# SCH_mpu6050_2024-04-15.net
KiCad netlist of a schematic drawn in EasyEDA
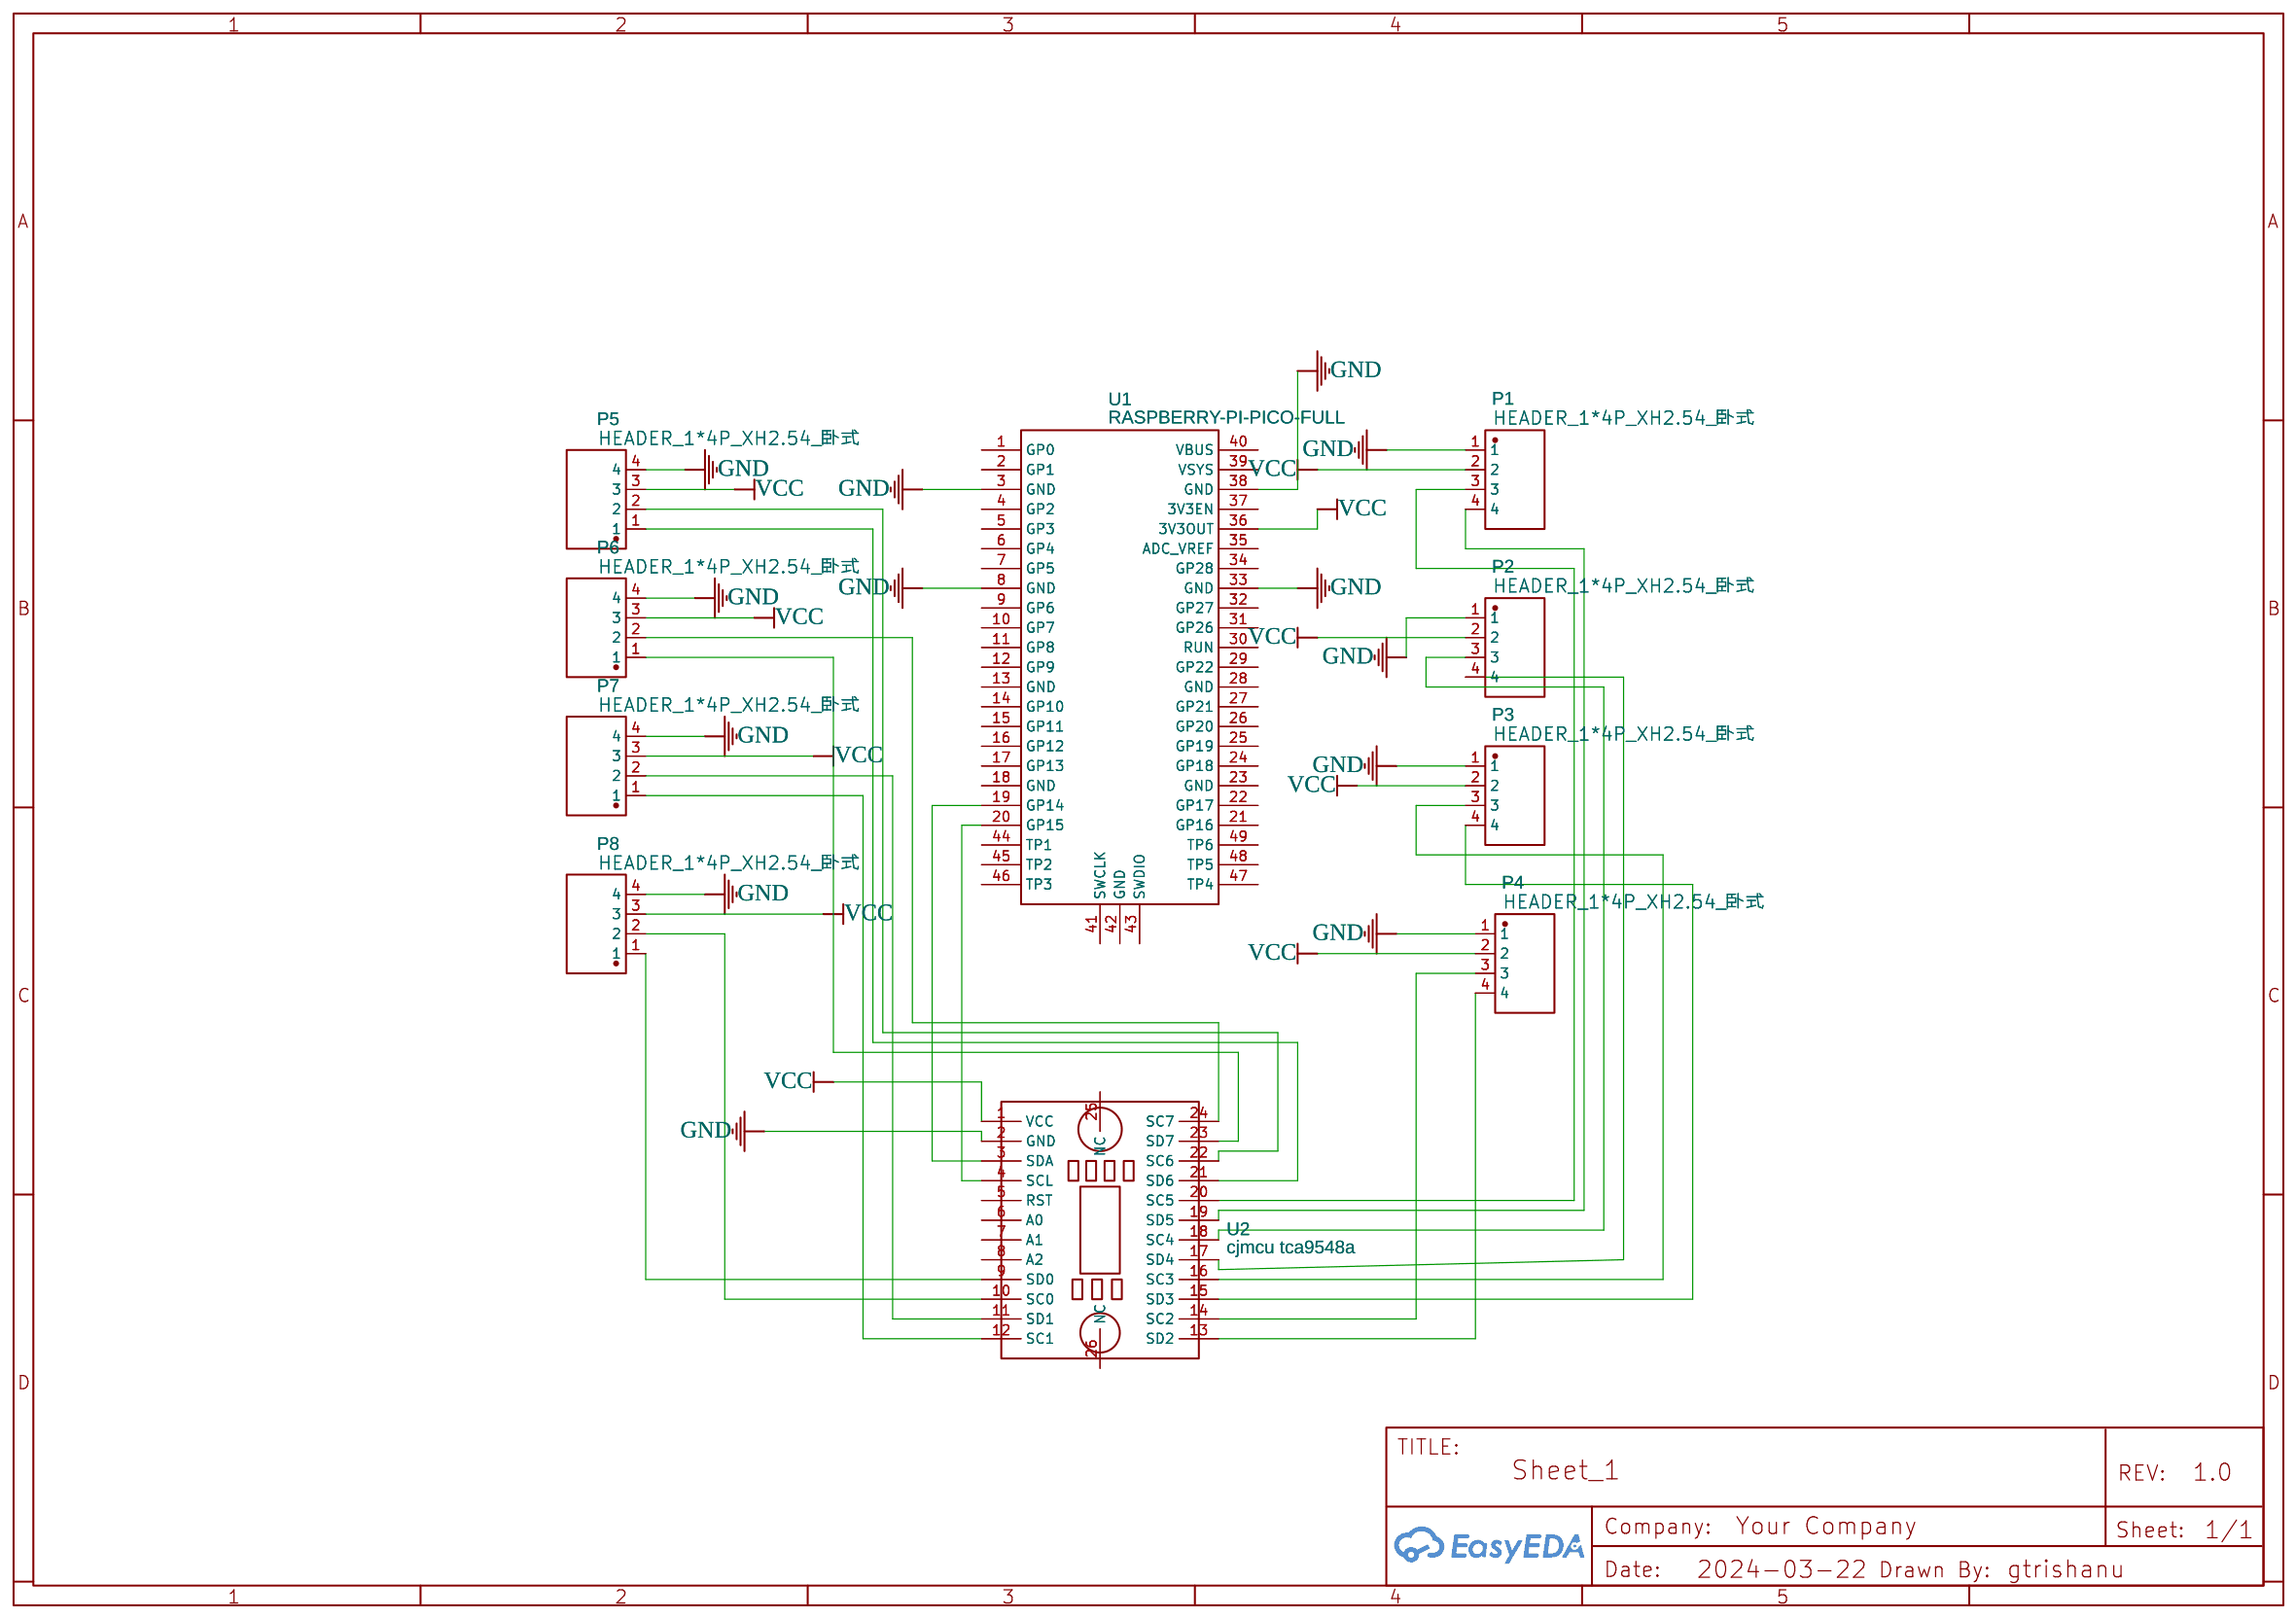
[diagram p0: schematic sheet]

(export (version "E")
  (design (tool "Eeschema 10.0.6"))
  (components
    (comp (ref "P1") (value "HEADER_1*4P_XH2.54_卧式") (libsource (lib "") (part "HEADER_1*4P_XH2.54_卧式")))
    (comp (ref "P2") (value "HEADER_1*4P_XH2.54_卧式") (libsource (lib "") (part "HEADER_1*4P_XH2.54_卧式")))
    (comp (ref "P3") (value "HEADER_1*4P_XH2.54_卧式") (libsource (lib "") (part "HEADER_1*4P_XH2.54_卧式")))
    (comp (ref "P4") (value "HEADER_1*4P_XH2.54_卧式") (libsource (lib "") (part "HEADER_1*4P_XH2.54_卧式")))
    (comp (ref "P5") (value "HEADER_1*4P_XH2.54_卧式") (libsource (lib "") (part "HEADER_1*4P_XH2.54_卧式_1")))
    (comp (ref "P6") (value "HEADER_1*4P_XH2.54_卧式") (libsource (lib "") (part "HEADER_1*4P_XH2.54_卧式_1")))
    (comp (ref "P7") (value "HEADER_1*4P_XH2.54_卧式") (libsource (lib "") (part "HEADER_1*4P_XH2.54_卧式_1")))
    (comp (ref "P8") (value "HEADER_1*4P_XH2.54_卧式") (libsource (lib "") (part "HEADER_1*4P_XH2.54_卧式_1")))
    (comp (ref "U1")
      (value "RASPBERRY-PI-PICO-FULL")
      (fields
        (field (name "Manufacturer Part") "Raspberry Pi Pico")
        (field (name "Manufacturer") "Raspberry Pi Foundation")
      )
      (libsource (lib "") (part "RASPBERRY-PI-PICO-FULL"))
    )
    (comp (ref "U2") (value "cjmcu tca9548a") (libsource (lib "") (part "cjmcu tca9548a")))
  )
  (nets
    (net (code "1") (name "GND") (class "Default")
      (node (ref "P1") (pin "1") (pinfunction "1_1") (pintype "unspecified"))
      (node (ref "P2") (pin "1") (pinfunction "1_1") (pintype "unspecified"))
      (node (ref "P3") (pin "1") (pinfunction "1_1") (pintype "unspecified"))
      (node (ref "P4") (pin "1") (pinfunction "1_1") (pintype "unspecified"))
      (node (ref "P5") (pin "4") (pinfunction "4_4") (pintype "unspecified"))
      (node (ref "P6") (pin "4") (pinfunction "4_4") (pintype "unspecified"))
      (node (ref "P7") (pin "4") (pinfunction "4_4") (pintype "unspecified"))
      (node (ref "P8") (pin "4") (pinfunction "4_4") (pintype "unspecified"))
      (node (ref "U1") (pin "3") (pinfunction "GND_3") (pintype "unspecified"))
      (node (ref "U1") (pin "33") (pinfunction "GND_33") (pintype "unspecified"))
      (node (ref "U1") (pin "38") (pinfunction "GND_38") (pintype "unspecified"))
      (node (ref "U1") (pin "8") (pinfunction "GND_8") (pintype "unspecified"))
      (node (ref "U2") (pin "2") (pinfunction "GND_2") (pintype "unspecified"))
    )
    (net (code "2") (name "Net-(U1-GP14)") (class "Default")
      (node (ref "U1") (pin "19") (pinfunction "GP14_19") (pintype "unspecified"))
      (node (ref "U2") (pin "3") (pinfunction "SDA_3") (pintype "unspecified"))
    )
    (net (code "3") (name "Net-(U1-GP15)") (class "Default")
      (node (ref "U1") (pin "20") (pinfunction "GP15_20") (pintype "unspecified"))
      (node (ref "U2") (pin "4") (pinfunction "SCL_4") (pintype "unspecified"))
    )
    (net (code "4") (name "Net-(U2-SC0)") (class "Default")
      (node (ref "P8") (pin "2") (pinfunction "2_2") (pintype "unspecified"))
      (node (ref "U2") (pin "10") (pinfunction "SC0_10") (pintype "unspecified"))
    )
    (net (code "5") (name "Net-(U2-SC1)") (class "Default")
      (node (ref "P7") (pin "1") (pinfunction "1_1") (pintype "unspecified"))
      (node (ref "U2") (pin "12") (pinfunction "SC1_12") (pintype "unspecified"))
    )
    (net (code "6") (name "Net-(U2-SC2)") (class "Default")
      (node (ref "P4") (pin "3") (pinfunction "3_3") (pintype "unspecified"))
      (node (ref "U2") (pin "14") (pinfunction "SC2_14") (pintype "unspecified"))
    )
    (net (code "7") (name "Net-(U2-SC3)") (class "Default")
      (node (ref "P3") (pin "3") (pinfunction "3_3") (pintype "unspecified"))
      (node (ref "U2") (pin "16") (pinfunction "SC3_16") (pintype "unspecified"))
    )
    (net (code "8") (name "Net-(U2-SC4)") (class "Default")
      (node (ref "P2") (pin "3") (pinfunction "3_3") (pintype "unspecified"))
      (node (ref "U2") (pin "18") (pinfunction "SC4_18") (pintype "unspecified"))
    )
    (net (code "9") (name "Net-(U2-SC5)") (class "Default")
      (node (ref "P1") (pin "3") (pinfunction "3_3") (pintype "unspecified"))
      (node (ref "U2") (pin "20") (pinfunction "SC5_20") (pintype "unspecified"))
    )
    (net (code "10") (name "Net-(U2-SC6)") (class "Default")
      (node (ref "P5") (pin "2") (pinfunction "2_2") (pintype "unspecified"))
      (node (ref "U2") (pin "22") (pinfunction "SC6_22") (pintype "unspecified"))
    )
    (net (code "11") (name "Net-(U2-SC7)") (class "Default")
      (node (ref "P6") (pin "2") (pinfunction "2_2") (pintype "unspecified"))
      (node (ref "U2") (pin "24") (pinfunction "SC7_24") (pintype "unspecified"))
    )
    (net (code "12") (name "Net-(U2-SD0)") (class "Default")
      (node (ref "P8") (pin "1") (pinfunction "1_1") (pintype "unspecified"))
      (node (ref "U2") (pin "9") (pinfunction "SD0_9") (pintype "unspecified"))
    )
    (net (code "13") (name "Net-(U2-SD1)") (class "Default")
      (node (ref "P7") (pin "2") (pinfunction "2_2") (pintype "unspecified"))
      (node (ref "U2") (pin "11") (pinfunction "SD1_11") (pintype "unspecified"))
    )
    (net (code "14") (name "Net-(U2-SD2)") (class "Default")
      (node (ref "P4") (pin "4") (pinfunction "4_4") (pintype "unspecified"))
      (node (ref "U2") (pin "13") (pinfunction "SD2_13") (pintype "unspecified"))
    )
    (net (code "15") (name "Net-(U2-SD3)") (class "Default")
      (node (ref "P3") (pin "4") (pinfunction "4_4") (pintype "unspecified"))
      (node (ref "U2") (pin "15") (pinfunction "SD3_15") (pintype "unspecified"))
    )
    (net (code "16") (name "Net-(U2-SD4)") (class "Default")
      (node (ref "P2") (pin "4") (pinfunction "4_4") (pintype "unspecified"))
      (node (ref "U2") (pin "17") (pinfunction "SD4_17") (pintype "unspecified"))
    )
    (net (code "17") (name "Net-(U2-SD5)") (class "Default")
      (node (ref "P1") (pin "4") (pinfunction "4_4") (pintype "unspecified"))
      (node (ref "U2") (pin "19") (pinfunction "SD5_19") (pintype "unspecified"))
    )
    (net (code "18") (name "Net-(U2-SD6)") (class "Default")
      (node (ref "P5") (pin "1") (pinfunction "1_1") (pintype "unspecified"))
      (node (ref "U2") (pin "21") (pinfunction "SD6_21") (pintype "unspecified"))
    )
    (net (code "19") (name "Net-(U2-SD7)") (class "Default")
      (node (ref "P6") (pin "1") (pinfunction "1_1") (pintype "unspecified"))
      (node (ref "U2") (pin "23") (pinfunction "SD7_23") (pintype "unspecified"))
    )
    (net (code "20") (name "VCC") (class "Default")
      (node (ref "P1") (pin "2") (pinfunction "2_2") (pintype "unspecified"))
      (node (ref "P2") (pin "2") (pinfunction "2_2") (pintype "unspecified"))
      (node (ref "P3") (pin "2") (pinfunction "2_2") (pintype "unspecified"))
      (node (ref "P4") (pin "2") (pinfunction "2_2") (pintype "unspecified"))
      (node (ref "P5") (pin "3") (pinfunction "3_3") (pintype "unspecified"))
      (node (ref "P6") (pin "3") (pinfunction "3_3") (pintype "unspecified"))
      (node (ref "P7") (pin "3") (pinfunction "3_3") (pintype "unspecified"))
      (node (ref "P8") (pin "3") (pinfunction "3_3") (pintype "unspecified"))
      (node (ref "U1") (pin "36") (pinfunction "3V3OUT_36") (pintype "unspecified"))
      (node (ref "U2") (pin "1") (pinfunction "VCC_1") (pintype "unspecified"))
    )
    (net (code "21") (name "unconnected-(U1-3V3EN-Pad37)") (class "Default")
      (node (ref "U1") (pin "37") (pinfunction "3V3EN_37") (pintype "unspecified"))
    )
    (net (code "22") (name "unconnected-(U1-ADC_VREF-Pad35)") (class "Default")
      (node (ref "U1") (pin "35") (pinfunction "ADC_VREF_35") (pintype "unspecified"))
    )
    (net (code "23") (name "unconnected-(U1-GND-Pad13)") (class "Default")
      (node (ref "U1") (pin "13") (pinfunction "GND_13") (pintype "unspecified"))
    )
    (net (code "24") (name "unconnected-(U1-GND-Pad18)") (class "Default")
      (node (ref "U1") (pin "18") (pinfunction "GND_18") (pintype "unspecified"))
    )
    (net (code "25") (name "unconnected-(U1-GND-Pad23)") (class "Default")
      (node (ref "U1") (pin "23") (pinfunction "GND_23") (pintype "unspecified"))
    )
    (net (code "26") (name "unconnected-(U1-GND-Pad28)") (class "Default")
      (node (ref "U1") (pin "28") (pinfunction "GND_28") (pintype "unspecified"))
    )
    (net (code "27") (name "unconnected-(U1-GND-Pad42)") (class "Default")
      (node (ref "U1") (pin "42") (pinfunction "GND_42") (pintype "unspecified"))
    )
    (net (code "28") (name "unconnected-(U1-GP0-Pad1)") (class "Default")
      (node (ref "U1") (pin "1") (pinfunction "GP0_1") (pintype "unspecified"))
    )
    (net (code "29") (name "unconnected-(U1-GP1-Pad2)") (class "Default")
      (node (ref "U1") (pin "2") (pinfunction "GP1_2") (pintype "unspecified"))
    )
    (net (code "30") (name "unconnected-(U1-GP2-Pad4)") (class "Default")
      (node (ref "U1") (pin "4") (pinfunction "GP2_4") (pintype "unspecified"))
    )
    (net (code "31") (name "unconnected-(U1-GP3-Pad5)") (class "Default")
      (node (ref "U1") (pin "5") (pinfunction "GP3_5") (pintype "unspecified"))
    )
    (net (code "32") (name "unconnected-(U1-GP4-Pad6)") (class "Default")
      (node (ref "U1") (pin "6") (pinfunction "GP4_6") (pintype "unspecified"))
    )
    (net (code "33") (name "unconnected-(U1-GP5-Pad7)") (class "Default")
      (node (ref "U1") (pin "7") (pinfunction "GP5_7") (pintype "unspecified"))
    )
    (net (code "34") (name "unconnected-(U1-GP6-Pad9)") (class "Default")
      (node (ref "U1") (pin "9") (pinfunction "GP6_9") (pintype "unspecified"))
    )
    (net (code "35") (name "unconnected-(U1-GP7-Pad10)") (class "Default")
      (node (ref "U1") (pin "10") (pinfunction "GP7_10") (pintype "unspecified"))
    )
    (net (code "36") (name "unconnected-(U1-GP8-Pad11)") (class "Default")
      (node (ref "U1") (pin "11") (pinfunction "GP8_11") (pintype "unspecified"))
    )
    (net (code "37") (name "unconnected-(U1-GP9-Pad12)") (class "Default")
      (node (ref "U1") (pin "12") (pinfunction "GP9_12") (pintype "unspecified"))
    )
    (net (code "38") (name "unconnected-(U1-GP10-Pad14)") (class "Default")
      (node (ref "U1") (pin "14") (pinfunction "GP10_14") (pintype "unspecified"))
    )
    (net (code "39") (name "unconnected-(U1-GP11-Pad15)") (class "Default")
      (node (ref "U1") (pin "15") (pinfunction "GP11_15") (pintype "unspecified"))
    )
    (net (code "40") (name "unconnected-(U1-GP12-Pad16)") (class "Default")
      (node (ref "U1") (pin "16") (pinfunction "GP12_16") (pintype "unspecified"))
    )
    (net (code "41") (name "unconnected-(U1-GP13-Pad17)") (class "Default")
      (node (ref "U1") (pin "17") (pinfunction "GP13_17") (pintype "unspecified"))
    )
    (net (code "42") (name "unconnected-(U1-GP16-Pad21)") (class "Default")
      (node (ref "U1") (pin "21") (pinfunction "GP16_21") (pintype "unspecified"))
    )
    (net (code "43") (name "unconnected-(U1-GP17-Pad22)") (class "Default")
      (node (ref "U1") (pin "22") (pinfunction "GP17_22") (pintype "unspecified"))
    )
    (net (code "44") (name "unconnected-(U1-GP18-Pad24)") (class "Default")
      (node (ref "U1") (pin "24") (pinfunction "GP18_24") (pintype "unspecified"))
    )
    (net (code "45") (name "unconnected-(U1-GP19-Pad25)") (class "Default")
      (node (ref "U1") (pin "25") (pinfunction "GP19_25") (pintype "unspecified"))
    )
    (net (code "46") (name "unconnected-(U1-GP20-Pad26)") (class "Default")
      (node (ref "U1") (pin "26") (pinfunction "GP20_26") (pintype "unspecified"))
    )
    (net (code "47") (name "unconnected-(U1-GP21-Pad27)") (class "Default")
      (node (ref "U1") (pin "27") (pinfunction "GP21_27") (pintype "unspecified"))
    )
    (net (code "48") (name "unconnected-(U1-GP22-Pad29)") (class "Default")
      (node (ref "U1") (pin "29") (pinfunction "GP22_29") (pintype "unspecified"))
    )
    (net (code "49") (name "unconnected-(U1-GP26-Pad31)") (class "Default")
      (node (ref "U1") (pin "31") (pinfunction "GP26_31") (pintype "unspecified"))
    )
    (net (code "50") (name "unconnected-(U1-GP27-Pad32)") (class "Default")
      (node (ref "U1") (pin "32") (pinfunction "GP27_32") (pintype "unspecified"))
    )
    (net (code "51") (name "unconnected-(U1-GP28-Pad34)") (class "Default")
      (node (ref "U1") (pin "34") (pinfunction "GP28_34") (pintype "unspecified"))
    )
    (net (code "52") (name "unconnected-(U1-RUN-Pad30)") (class "Default")
      (node (ref "U1") (pin "30") (pinfunction "RUN_30") (pintype "unspecified"))
    )
    (net (code "53") (name "unconnected-(U1-SWCLK-Pad41)") (class "Default")
      (node (ref "U1") (pin "41") (pinfunction "SWCLK_41") (pintype "unspecified"))
    )
    (net (code "54") (name "unconnected-(U1-SWDIO-Pad43)") (class "Default")
      (node (ref "U1") (pin "43") (pinfunction "SWDIO_43") (pintype "unspecified"))
    )
    (net (code "55") (name "unconnected-(U1-TP1-Pad44)") (class "Default")
      (node (ref "U1") (pin "44") (pinfunction "TP1_44") (pintype "unspecified"))
    )
    (net (code "56") (name "unconnected-(U1-TP2-Pad45)") (class "Default")
      (node (ref "U1") (pin "45") (pinfunction "TP2_45") (pintype "unspecified"))
    )
    (net (code "57") (name "unconnected-(U1-TP3-Pad46)") (class "Default")
      (node (ref "U1") (pin "46") (pinfunction "TP3_46") (pintype "unspecified"))
    )
    (net (code "58") (name "unconnected-(U1-TP4-Pad47)") (class "Default")
      (node (ref "U1") (pin "47") (pinfunction "TP4_47") (pintype "unspecified"))
    )
    (net (code "59") (name "unconnected-(U1-TP5-Pad48)") (class "Default")
      (node (ref "U1") (pin "48") (pinfunction "TP5_48") (pintype "unspecified"))
    )
    (net (code "60") (name "unconnected-(U1-TP6-Pad49)") (class "Default")
      (node (ref "U1") (pin "49") (pinfunction "TP6_49") (pintype "unspecified"))
    )
    (net (code "61") (name "unconnected-(U1-VBUS-Pad40)") (class "Default")
      (node (ref "U1") (pin "40") (pinfunction "VBUS_40") (pintype "unspecified"))
    )
    (net (code "62") (name "unconnected-(U1-VSYS-Pad39)") (class "Default")
      (node (ref "U1") (pin "39") (pinfunction "VSYS_39") (pintype "unspecified"))
    )
    (net (code "63") (name "unconnected-(U2-A0-Pad6)") (class "Default")
      (node (ref "U2") (pin "6") (pinfunction "A0_6") (pintype "unspecified"))
    )
    (net (code "64") (name "unconnected-(U2-A1-Pad7)") (class "Default")
      (node (ref "U2") (pin "7") (pinfunction "A1_7") (pintype "unspecified"))
    )
    (net (code "65") (name "unconnected-(U2-A2-Pad8)") (class "Default")
      (node (ref "U2") (pin "8") (pinfunction "A2_8") (pintype "unspecified"))
    )
    (net (code "66") (name "unconnected-(U2-NC-Pad25)") (class "Default")
      (node (ref "U2") (pin "25") (pinfunction "NC_25") (pintype "unspecified"))
    )
    (net (code "67") (name "unconnected-(U2-NC-Pad26)") (class "Default")
      (node (ref "U2") (pin "26") (pinfunction "NC_26") (pintype "unspecified"))
    )
    (net (code "68") (name "unconnected-(U2-RST-Pad5)") (class "Default")
      (node (ref "U2") (pin "5") (pinfunction "RST_5") (pintype "unspecified"))
    )
  )
)
